# ignitor_mux.net
KiCad netlist of a schematic drawn in EAGLE
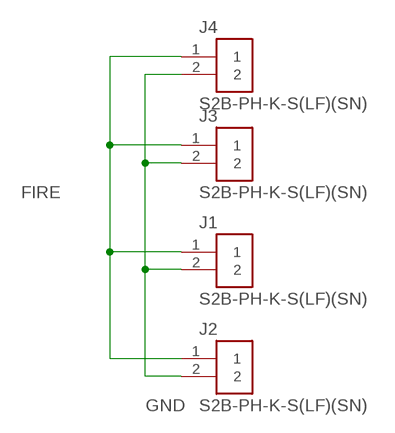
[diagram p0: schematic, sheet 1]

(export (version "E")
  (design (tool "Eeschema 10.0.6"))
  (components
    (comp (ref "J1")
      (value "S2B-PH-K-S(LF)(SN)")
      (footprint "eagle-import:S2B-PH-K-S(LF)(SN)")
      (fields
        (field (name "DIGI_KEY_PART_NUMBER") "455-1719-ND")
        (field (name "MANUFACTURER") "JST Sales America Inc.")
        (field (name "CREATED_BY") "PCBLayout.com")
      )
      (libsource (lib "eagle-import") (part "S2B-PH-K-S(LF)(SN)"))
    )
    (comp (ref "J2")
      (value "S2B-PH-K-S(LF)(SN)")
      (footprint "eagle-import:S2B-PH-K-S(LF)(SN)")
      (fields
        (field (name "DIGI_KEY_PART_NUMBER") "455-1719-ND")
        (field (name "MANUFACTURER") "JST Sales America Inc.")
        (field (name "CREATED_BY") "PCBLayout.com")
      )
      (libsource (lib "eagle-import") (part "S2B-PH-K-S(LF)(SN)"))
    )
    (comp (ref "J3")
      (value "S2B-PH-K-S(LF)(SN)")
      (footprint "eagle-import:S2B-PH-K-S(LF)(SN)")
      (fields
        (field (name "DIGI_KEY_PART_NUMBER") "455-1719-ND")
        (field (name "MANUFACTURER") "JST Sales America Inc.")
        (field (name "CREATED_BY") "PCBLayout.com")
      )
      (libsource (lib "eagle-import") (part "S2B-PH-K-S(LF)(SN)"))
    )
    (comp (ref "J4")
      (value "S2B-PH-K-S(LF)(SN)")
      (footprint "eagle-import:S2B-PH-K-S(LF)(SN)")
      (fields
        (field (name "DIGI_KEY_PART_NUMBER") "455-1719-ND")
        (field (name "MANUFACTURER") "JST Sales America Inc.")
        (field (name "CREATED_BY") "PCBLayout.com")
      )
      (libsource (lib "eagle-import") (part "S2B-PH-K-S(LF)(SN)"))
    )
  )
  (nets
    (net (code "1") (name "/FIRE") (class "Default")
      (node (ref "J1") (pin "1") (pinfunction "1_1") (pintype "passive"))
      (node (ref "J2") (pin "1") (pinfunction "1_1") (pintype "passive"))
      (node (ref "J3") (pin "1") (pinfunction "1_1") (pintype "passive"))
      (node (ref "J4") (pin "1") (pinfunction "1_1") (pintype "passive"))
    )
    (net (code "2") (name "/GND") (class "Default")
      (node (ref "J1") (pin "2") (pinfunction "2_2") (pintype "passive"))
      (node (ref "J2") (pin "2") (pinfunction "2_2") (pintype "passive"))
      (node (ref "J3") (pin "2") (pinfunction "2_2") (pintype "passive"))
      (node (ref "J4") (pin "2") (pinfunction "2_2") (pintype "passive"))
    )
  )
)
